# Signal_Conditioner.net
KiCad netlist of a schematic drawn in Altium Designer
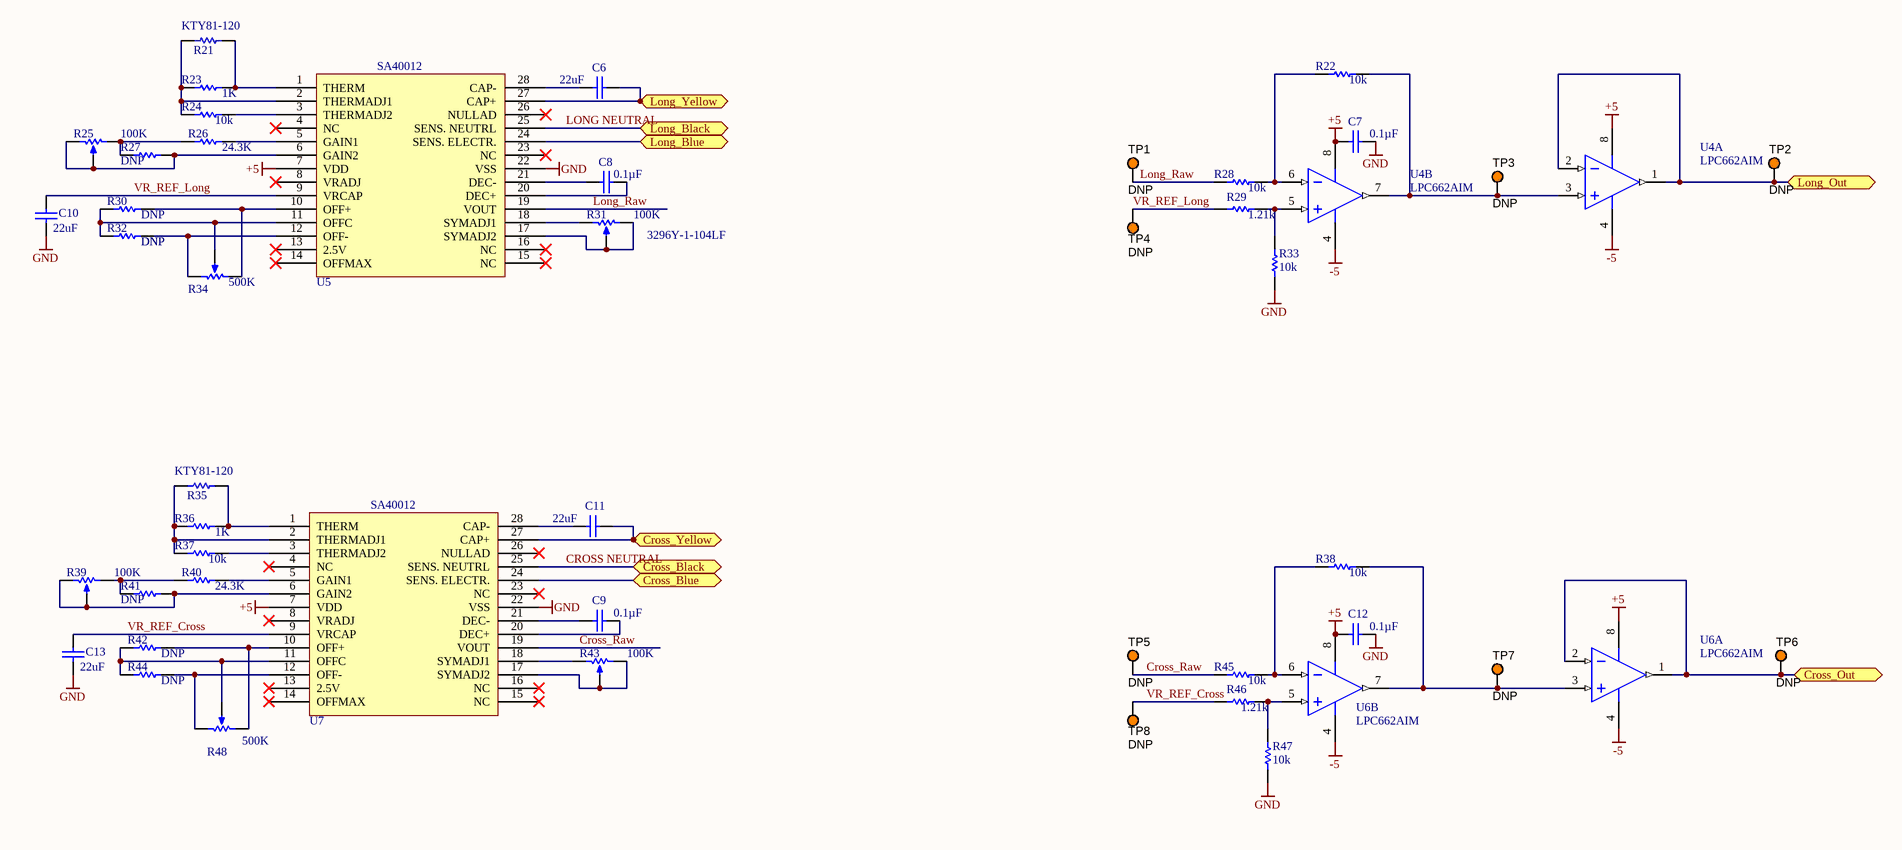
[diagram p0: Signal_Conditioner.SchDoc]

(export (version "E")
  (design (tool "Eeschema 10.0.6"))
  (components
    (comp (ref "C6")
      (value "22uF")
      (footprint "CAPC0805(2012)145_N")
      (description "CAP CER 22UF 16V X5R 0805")
      (fields
        (field (name "MANUFACTURER") "Murata Electronics North America")
        (field (name "MANUFACTURER PART NUMBER") "GRM219R61C226ME15L")
      )
      (libsource (lib "Altium Content Vault") (part "CMP-1036-04795-1"))
    )
    (comp (ref "C7")
      (value "CAP CER 0.1UF 25V X7R 0805")
      (footprint "CAPC0805(2012)145_N")
      (fields
        (field (name "MANUFACTURER") "Murata Electronics North America")
        (field (name "MANUFACTURER PART NUMBER") "GRM21BR71E104KA01L")
        (field (name "CAPACITANCE") "0.1µF")
        (field (name "TOLERANCE") "±10%")
      )
      (libsource (lib "Altium Content Vault") (part "CMP-1036-04795-1"))
    )
    (comp (ref "C8")
      (value "CAP CER 0.1UF 25V X7R 0805")
      (footprint "CAPC0805(2012)145_N")
      (fields
        (field (name "MANUFACTURER") "Murata Electronics North America")
        (field (name "MANUFACTURER PART NUMBER") "GRM21BR71E104KA01L")
        (field (name "CAPACITANCE") "0.1µF")
        (field (name "TOLERANCE") "±10%")
      )
      (libsource (lib "Altium Content Vault") (part "CMP-1036-04795-1"))
    )
    (comp (ref "C9")
      (value "CAP CER 0.1UF 25V X7R 0805")
      (footprint "CAPC0805(2012)145_N")
      (fields
        (field (name "MANUFACTURER") "Murata Electronics North America")
        (field (name "MANUFACTURER PART NUMBER") "GRM21BR71E104KA01L")
        (field (name "CAPACITANCE") "0.1µF")
        (field (name "TOLERANCE") "±10%")
      )
      (libsource (lib "Altium Content Vault") (part "CMP-1036-04795-1"))
    )
    (comp (ref "C10")
      (value "22uF")
      (footprint "CAPC0805(2012)145_N")
      (description "CAP CER 22UF 16V X5R 0805")
      (fields
        (field (name "MANUFACTURER") "Murata Electronics North America")
        (field (name "MANUFACTURER PART NUMBER") "GRM219R61C226ME15L")
      )
      (libsource (lib "Altium Content Vault") (part "CMP-1036-04795-1"))
    )
    (comp (ref "C11")
      (value "22uF")
      (footprint "CAPC0805(2012)145_N")
      (description "CAP CER 22UF 16V X5R 0805")
      (fields
        (field (name "MANUFACTURER") "Murata Electronics North America")
        (field (name "MANUFACTURER PART NUMBER") "GRM219R61C226ME15L")
      )
      (libsource (lib "Altium Content Vault") (part "CMP-1036-04795-1"))
    )
    (comp (ref "C12")
      (value "CAP CER 0.1UF 25V X7R 0805")
      (footprint "CAPC0805(2012)145_N")
      (fields
        (field (name "MANUFACTURER") "Murata Electronics North America")
        (field (name "MANUFACTURER PART NUMBER") "GRM21BR71E104KA01L")
        (field (name "CAPACITANCE") "0.1µF")
        (field (name "TOLERANCE") "±10%")
      )
      (libsource (lib "Altium Content Vault") (part "CMP-1036-04795-1"))
    )
    (comp (ref "C13")
      (value "22uF")
      (footprint "CAPC0805(2012)145_N")
      (description "CAP CER 22UF 16V X5R 0805")
      (fields
        (field (name "MANUFACTURER") "Murata Electronics North America")
        (field (name "MANUFACTURER PART NUMBER") "GRM219R61C226ME15L")
      )
      (libsource (lib "Altium Content Vault") (part "CMP-1036-04795-1"))
    )
    (comp (ref "R21")
      (value "KTY81-120")
      (footprint "KTY81-120")
      (description "THERMISTOR PTC 1K OHM PBCYT2")
      (fields
        (field (name "MANUFACTURER") "NXP USA Inc.")
        (field (name "MANUFACTURER PART NUMBER") "KTY81/120,112")
      )
      (libsource (lib "ZLS_Schematic_lib") (part "KTY81-120"))
    )
    (comp (ref "R22")
      (value "10k")
      (footprint "RESC0805(2012)_L")
      (description "RES SMD 10K OHM 1% 1/8W 0805")
      (fields
        (field (name "MANUFACTURER") "Vishay Dale")
        (field (name "MANUFACTURER PART NUMBER") "CRCW080510K0FKEA")
      )
      (libsource (lib "Altium Content Vault") (part "CMP-1013-00393-1"))
    )
    (comp (ref "R23")
      (value "1K")
      (footprint "RESC0805(2012)_L")
      (description "RES SMD 1K OHM 1% 1/8W 0805")
      (fields
        (field (name "MANUFACTURER") "Vishay Dale")
        (field (name "MANUFACTURER PART NUMBER") "CRCW08051K00FKEA")
      )
      (libsource (lib "Altium Content Vault") (part "CMP-1013-00393-1"))
    )
    (comp (ref "R24")
      (value "10k")
      (footprint "RESC0805(2012)_L")
      (description "RES SMD 10K OHM 1% 1/8W 0805")
      (fields
        (field (name "MANUFACTURER") "Vishay Dale")
        (field (name "MANUFACTURER PART NUMBER") "CRCW080510K0FKEA")
      )
      (libsource (lib "Altium Content Vault") (part "CMP-1013-00393-1"))
    )
    (comp (ref "R25")
      (value "100K")
      (footprint "Trimmer 2.54")
      (description "TRIMMER 5K OHM 0.25W PC PIN")
      (fields
        (field (name "MANUFACTURER") "Bourns Inc.")
        (field (name "MANUFACTURER PART NUMBER") "3296Y-1-104LF")
      )
      (libsource (lib "ZLS_Schematic_lib") (part "Trimmer"))
    )
    (comp (ref "R26")
      (value "24.3K")
      (footprint "RESC0805(2012)_L")
      (description "RES SMD 24.3K OHM 1% 1/8W 0805")
      (fields
        (field (name "MANUFACTURER") "Vishay Dale")
        (field (name "MANUFACTURER PART NUMBER") "CRCW080524K3FKEA")
      )
      (libsource (lib "Altium Content Vault") (part "CMP-1013-00393-1"))
    )
    (comp (ref "R27")
      (value "DNP")
      (footprint "RESC0805(2012)_L")
      (description "RES SMD 10K OHM 1% 1/8W 0805")
      (fields
        (field (name "MANUFACTURER") "Vishay Dale")
        (field (name "MANUFACTURER PART NUMBER") "CRCW080510K0FKEA")
      )
      (libsource (lib "Altium Content Vault") (part "CMP-1013-00393-1"))
    )
    (comp (ref "R28")
      (value "10k")
      (footprint "RESC0805(2012)_L")
      (description "RES SMD 10K OHM 1% 1/8W 0805")
      (fields
        (field (name "MANUFACTURER") "Vishay Dale")
        (field (name "MANUFACTURER PART NUMBER") "CRCW080510K0FKEA")
      )
      (libsource (lib "Altium Content Vault") (part "CMP-1013-00393-1"))
    )
    (comp (ref "R29")
      (value "1.21k")
      (footprint "RESC0805(2012)_L")
      (description "RES SMD 1.21K OHM 1% 1/8W 0805")
      (fields
        (field (name "MANUFACTURER") "Vishay Dale")
        (field (name "MANUFACTURER PART NUMBER") "CRCW08051K21FKEA")
      )
      (libsource (lib "Altium Content Vault") (part "CMP-1013-00393-1"))
    )
    (comp (ref "R30")
      (value "DNP")
      (footprint "RESC0805(2012)_L")
      (description "RES SMD 249K OHM 1% 1/8W 0805")
      (fields
        (field (name "MANUFACTURER") "Vishay Dale")
        (field (name "MANUFACTURER PART NUMBER") "CRCW0805249KFKECC")
      )
      (libsource (lib "Altium Content Vault") (part "CMP-1013-00393-1"))
    )
    (comp (ref "R31")
      (value "100K")
      (footprint "Trimmer 2.54")
      (description "TRIMMER 5K OHM 0.25W PC PIN")
      (fields
        (field (name "MANUFACTURER") "Bourns Inc.")
        (field (name "MANUFACTURER PART NUMBER") "3296Y-1-104LF")
      )
      (libsource (lib "ZLS_Schematic_lib") (part "Trimmer"))
    )
    (comp (ref "R32")
      (value "DNP")
      (footprint "RESC0805(2012)_L")
      (description "RES SMD 249K OHM 1% 1/8W 0805")
      (fields
        (field (name "MANUFACTURER") "Vishay Dale")
        (field (name "MANUFACTURER PART NUMBER") "CRCW0805249KFKECC")
      )
      (libsource (lib "Altium Content Vault") (part "CMP-1013-00393-1"))
    )
    (comp (ref "R33")
      (value "10k")
      (footprint "RESC0805(2012)_L")
      (description "RES SMD 10K OHM 1% 1/8W 0805")
      (fields
        (field (name "MANUFACTURER") "Vishay Dale")
        (field (name "MANUFACTURER PART NUMBER") "CRCW080510K0FKEA")
      )
      (libsource (lib "Altium Content Vault") (part "CMP-1013-00393-1"))
    )
    (comp (ref "R34")
      (value "500K")
      (footprint "Trimmer 2.54")
      (description "TRIMMER 500K OHM 0.5W PC PIN TOP")
      (fields
        (field (name "MANUFACTURER") "Bourns Inc.")
        (field (name "MANUFACTURER PART NUMBER") "3296Y-1-504LF")
      )
      (libsource (lib "ZLS_Schematic_lib") (part "Trimmer"))
    )
    (comp (ref "R35")
      (value "KTY81-120")
      (footprint "KTY81-120")
      (description "THERMISTOR PTC 1K OHM PBCYT2")
      (fields
        (field (name "MANUFACTURER") "NXP USA Inc.")
        (field (name "MANUFACTURER PART NUMBER") "KTY81/120,112")
      )
      (libsource (lib "ZLS_Schematic_lib") (part "KTY81-120"))
    )
    (comp (ref "R36")
      (value "1K")
      (footprint "RESC0805(2012)_L")
      (description "RES SMD 1K OHM 1% 1/8W 0805")
      (fields
        (field (name "MANUFACTURER") "Vishay Dale")
        (field (name "MANUFACTURER PART NUMBER") "CRCW08051K00FKEA")
      )
      (libsource (lib "Altium Content Vault") (part "CMP-1013-00393-1"))
    )
    (comp (ref "R37")
      (value "10k")
      (footprint "RESC0805(2012)_L")
      (description "RES SMD 10K OHM 1% 1/8W 0805")
      (fields
        (field (name "MANUFACTURER") "Vishay Dale")
        (field (name "MANUFACTURER PART NUMBER") "CRCW080510K0FKEA")
      )
      (libsource (lib "Altium Content Vault") (part "CMP-1013-00393-1"))
    )
    (comp (ref "R38")
      (value "10k")
      (footprint "RESC0805(2012)_L")
      (description "RES SMD 10K OHM 1% 1/8W 0805")
      (fields
        (field (name "MANUFACTURER") "Vishay Dale")
        (field (name "MANUFACTURER PART NUMBER") "CRCW080510K0FKEA")
      )
      (libsource (lib "Altium Content Vault") (part "CMP-1013-00393-1"))
    )
    (comp (ref "R39")
      (value "100K")
      (footprint "Trimmer 2.54")
      (description "TRIMMER 5K OHM 0.25W PC PIN")
      (fields
        (field (name "MANUFACTURER") "Bourns Inc.")
        (field (name "MANUFACTURER PART NUMBER") "3296Y-1-104LF")
      )
      (libsource (lib "ZLS_Schematic_lib") (part "Trimmer"))
    )
    (comp (ref "R40")
      (value "24.3K")
      (footprint "RESC0805(2012)_L")
      (description "RES SMD 24.3K OHM 1% 1/8W 0805")
      (fields
        (field (name "MANUFACTURER") "Vishay Dale")
        (field (name "MANUFACTURER PART NUMBER") "CRCW080524K3FKEA")
      )
      (libsource (lib "Altium Content Vault") (part "CMP-1013-00393-1"))
    )
    (comp (ref "R41")
      (value "DNP")
      (footprint "RESC0805(2012)_L")
      (description "RES SMD 10K OHM 1% 1/8W 0805")
      (fields
        (field (name "MANUFACTURER") "Vishay Dale")
        (field (name "MANUFACTURER PART NUMBER") "CRCW080510K0FKEA")
      )
      (libsource (lib "Altium Content Vault") (part "CMP-1013-00393-1"))
    )
    (comp (ref "R42")
      (value "DNP")
      (footprint "RESC0805(2012)_L")
      (description "RES SMD 249K OHM 1% 1/8W 0805")
      (fields
        (field (name "MANUFACTURER") "Vishay Dale")
        (field (name "MANUFACTURER PART NUMBER") "CRCW0805249KFKECC")
      )
      (libsource (lib "Altium Content Vault") (part "CMP-1013-00393-1"))
    )
    (comp (ref "R43")
      (value "100K")
      (footprint "Trimmer 2.54")
      (description "TRIMMER 5K OHM 0.25W PC PIN")
      (fields
        (field (name "MANUFACTURER") "Bourns Inc.")
        (field (name "MANUFACTURER PART NUMBER") "3296Y-1-104LF")
      )
      (libsource (lib "ZLS_Schematic_lib") (part "Trimmer"))
    )
    (comp (ref "R44")
      (value "DNP")
      (footprint "RESC0805(2012)_L")
      (description "RES SMD 249K OHM 1% 1/8W 0805")
      (fields
        (field (name "MANUFACTURER") "Vishay Dale")
        (field (name "MANUFACTURER PART NUMBER") "CRCW0805249KFKECC")
      )
      (libsource (lib "Altium Content Vault") (part "CMP-1013-00393-1"))
    )
    (comp (ref "R45")
      (value "10k")
      (footprint "RESC0805(2012)_L")
      (description "RES SMD 10K OHM 1% 1/8W 0805")
      (fields
        (field (name "MANUFACTURER") "Vishay Dale")
        (field (name "MANUFACTURER PART NUMBER") "CRCW080510K0FKEA")
      )
      (libsource (lib "Altium Content Vault") (part "CMP-1013-00393-1"))
    )
    (comp (ref "R46")
      (value "1.21k")
      (footprint "RESC0805(2012)_L")
      (description "RES SMD 1.21K OHM 1% 1/8W 0805")
      (fields
        (field (name "MANUFACTURER") "Vishay Dale")
        (field (name "MANUFACTURER PART NUMBER") "CRCW08051K21FKEA")
      )
      (libsource (lib "Altium Content Vault") (part "CMP-1013-00393-1"))
    )
    (comp (ref "R47")
      (value "10k")
      (footprint "RESC0805(2012)_L")
      (description "RES SMD 10K OHM 1% 1/8W 0805")
      (fields
        (field (name "MANUFACTURER") "Vishay Dale")
        (field (name "MANUFACTURER PART NUMBER") "CRCW080510K0FKEA")
      )
      (libsource (lib "Altium Content Vault") (part "CMP-1013-00393-1"))
    )
    (comp (ref "R48")
      (value "500K")
      (footprint "Trimmer 2.54")
      (description "TRIMMER 500K OHM 0.5W PC PIN TOP")
      (fields
        (field (name "MANUFACTURER") "Bourns Inc.")
        (field (name "MANUFACTURER PART NUMBER") "3296Y-1-504LF")
      )
      (libsource (lib "ZLS_Schematic_lib") (part "Trimmer"))
    )
    (comp (ref "TP1")
      (value "DNP")
      (footprint "KSTN-5003")
      (description "Test Point, Orange, 1-Pin THD, RoHS")
      (fields
        (field (name "MANUFACTURER") "Keystone Electronics")
        (field (name "MANUFACTURER PART NUMBER") "5003")
      )
      (libsource (lib "Altium Content Vault") (part "CMP-1672-00009-1"))
    )
    (comp (ref "TP2")
      (value "DNP")
      (footprint "KSTN-5003")
      (description "Test Point, Orange, 1-Pin THD, RoHS")
      (fields
        (field (name "MANUFACTURER") "Keystone Electronics")
        (field (name "MANUFACTURER PART NUMBER") "5003")
      )
      (libsource (lib "Altium Content Vault") (part "CMP-1672-00009-1"))
    )
    (comp (ref "TP3")
      (value "DNP")
      (footprint "KSTN-5003")
      (description "Test Point, Orange, 1-Pin THD, RoHS")
      (fields
        (field (name "MANUFACTURER") "Keystone Electronics")
        (field (name "MANUFACTURER PART NUMBER") "5003")
      )
      (libsource (lib "Altium Content Vault") (part "CMP-1672-00009-1"))
    )
    (comp (ref "TP4")
      (value "DNP")
      (footprint "KSTN-5003")
      (description "Test Point, Orange, 1-Pin THD, RoHS")
      (fields
        (field (name "MANUFACTURER") "Keystone Electronics")
        (field (name "MANUFACTURER PART NUMBER") "5003")
      )
      (libsource (lib "Altium Content Vault") (part "CMP-1672-00009-1"))
    )
    (comp (ref "TP5")
      (value "DNP")
      (footprint "KSTN-5003")
      (description "Test Point, Orange, 1-Pin THD, RoHS")
      (fields
        (field (name "MANUFACTURER") "Keystone Electronics")
        (field (name "MANUFACTURER PART NUMBER") "5003")
      )
      (libsource (lib "Altium Content Vault") (part "CMP-1672-00009-1"))
    )
    (comp (ref "TP6")
      (value "DNP")
      (footprint "KSTN-5003")
      (description "Test Point, Orange, 1-Pin THD, RoHS")
      (fields
        (field (name "MANUFACTURER") "Keystone Electronics")
        (field (name "MANUFACTURER PART NUMBER") "5003")
      )
      (libsource (lib "Altium Content Vault") (part "CMP-1672-00009-1"))
    )
    (comp (ref "TP7")
      (value "DNP")
      (footprint "KSTN-5003")
      (description "Test Point, Orange, 1-Pin THD, RoHS")
      (fields
        (field (name "MANUFACTURER") "Keystone Electronics")
        (field (name "MANUFACTURER PART NUMBER") "5003")
      )
      (libsource (lib "Altium Content Vault") (part "CMP-1672-00009-1"))
    )
    (comp (ref "TP8")
      (value "DNP")
      (footprint "KSTN-5003")
      (description "Test Point, Orange, 1-Pin THD, RoHS")
      (fields
        (field (name "MANUFACTURER") "Keystone Electronics")
        (field (name "MANUFACTURER PART NUMBER") "5003")
      )
      (libsource (lib "Altium Content Vault") (part "CMP-1672-00009-1"))
    )
    (comp (ref "U4")
      (value "LPC662AIM")
      (footprint "D0008A_M")
      (description "Low Power CMOS Dual Operational Amplifier, 8-pin Narrow SOIC")
      (fields (field (name "MANUFACTURER") "Texas Instruments"))
      (libsource (lib "Altium Content Vault") (part "AMP-OPA-LM6132-8"))
    )
    (comp (ref "U5")
      (value "SA40012")
      (footprint "SA40012")
      (description "Single Axix CMOS Signal Conditioning Module")
      (fields (field (name "MANUFACTURER") "Spectron") (field (name "MANUFACTURER PART NUMBER") "A40012"))
      (libsource (lib "ZLS_Schematic_lib") (part "SA40012"))
    )
    (comp (ref "U6")
      (value "LPC662AIM")
      (footprint "D0008A_M")
      (description "Low Power CMOS Dual Operational Amplifier, 8-pin Narrow SOIC")
      (fields
        (field (name "MANUFACTURER") "Texas Instruments")
        (field (name "MANUFACTURER PART NUMBER") "LPC662AIMX/NOPB")
      )
      (libsource (lib "Altium Content Vault") (part "CMP-0055-00867-3"))
    )
    (comp (ref "U7")
      (value "SA40012")
      (footprint "SA40012")
      (description "Single Axix CMOS Signal Conditioning Module")
      (fields (field (name "MANUFACTURER") "Spectron") (field (name "MANUFACTURER PART NUMBER") "A40012"))
      (libsource (lib "ZLS_Schematic_lib") (part "SA40012"))
    )
  )
  (nets
    (net (code "1") (name "+5") (class "Default")
      (node (ref "C12") (pin "1") (pinfunction "1_1") (pintype "passive"))
      (node (ref "C7") (pin "1") (pinfunction "1_1") (pintype "passive"))
      (node (ref "U4") (pin "8") (pinfunction "V+_8") (pintype "power_in"))
      (node (ref "U5") (pin "7") (pinfunction "VDD_7") (pintype "passive"))
      (node (ref "U6") (pin "8") (pinfunction "V+_8") (pintype "power_in"))
      (node (ref "U7") (pin "7") (pinfunction "VDD_7") (pintype "passive"))
    )
    (net (code "2") (name "-5") (class "Default")
      (node (ref "U4") (pin "4") (pinfunction "V-_4") (pintype "power_in"))
      (node (ref "U6") (pin "4") (pinfunction "V-_4") (pintype "power_in"))
    )
    (net (code "3") (name "/CROSS NEUTRAL") (class "Default")
      (node (ref "U7") (pin "25") (pinfunction "SENS._NEUTRL_25") (pintype "passive"))
    )
    (net (code "4") (name "/Cross_Blue") (class "Default")
      (node (ref "U7") (pin "24") (pinfunction "SENS._ELECTR._24") (pintype "passive"))
    )
    (net (code "5") (name "/Cross_Out") (class "Default")
      (node (ref "TP6") (pin "1") (pinfunction "1_1") (pintype "passive"))
      (node (ref "U6") (pin "1") (pinfunction "OUTA_1") (pintype "output"))
      (node (ref "U6") (pin "2") (pinfunction "INA-_2") (pintype "input"))
    )
    (net (code "6") (name "/Cross_Raw") (class "Default")
      (node (ref "R45") (pin "1") (pinfunction "1_1") (pintype "passive"))
      (node (ref "TP5") (pin "1") (pinfunction "1_1") (pintype "passive"))
      (node (ref "U7") (pin "19") (pinfunction "VOUT_19") (pintype "passive"))
    )
    (net (code "7") (name "/Cross_Yellow") (class "Default")
      (node (ref "C11") (pin "2") (pinfunction "2_2") (pintype "passive"))
      (node (ref "U7") (pin "27") (pinfunction "CAP+_27") (pintype "passive"))
    )
    (net (code "8") (name "/LONG NEUTRAL") (class "Default")
      (node (ref "U5") (pin "25") (pinfunction "SENS._NEUTRL_25") (pintype "passive"))
    )
    (net (code "9") (name "/Long_Blue") (class "Default")
      (node (ref "U5") (pin "24") (pinfunction "SENS._ELECTR._24") (pintype "passive"))
    )
    (net (code "10") (name "/Long_Out") (class "Default")
      (node (ref "TP2") (pin "1") (pinfunction "1_1") (pintype "passive"))
      (node (ref "U4") (pin "1") (pinfunction "OUTA_1") (pintype "output"))
      (node (ref "U4") (pin "2") (pinfunction "INA-_2") (pintype "input"))
    )
    (net (code "11") (name "/Long_Raw") (class "Default")
      (node (ref "R28") (pin "1") (pinfunction "1_1") (pintype "passive"))
      (node (ref "TP1") (pin "1") (pinfunction "1_1") (pintype "passive"))
      (node (ref "U5") (pin "19") (pinfunction "VOUT_19") (pintype "passive"))
    )
    (net (code "12") (name "/Long_Yellow") (class "Default")
      (node (ref "C6") (pin "2") (pinfunction "2_2") (pintype "passive"))
      (node (ref "U5") (pin "27") (pinfunction "CAP+_27") (pintype "passive"))
    )
    (net (code "13") (name "/VR_REF_Cross") (class "Default")
      (node (ref "C13") (pin "1") (pinfunction "1_1") (pintype "passive"))
      (node (ref "R46") (pin "2") (pinfunction "2_2") (pintype "passive"))
      (node (ref "TP8") (pin "1") (pinfunction "1_1") (pintype "passive"))
      (node (ref "U7") (pin "9") (pinfunction "VRCAP_9") (pintype "passive"))
    )
    (net (code "14") (name "/VR_REF_Long") (class "Default")
      (node (ref "C10") (pin "1") (pinfunction "1_1") (pintype "passive"))
      (node (ref "R29") (pin "2") (pinfunction "2_2") (pintype "passive"))
      (node (ref "TP4") (pin "1") (pinfunction "1_1") (pintype "passive"))
      (node (ref "U5") (pin "9") (pinfunction "VRCAP_9") (pintype "passive"))
    )
    (net (code "15") (name "GND") (class "Default")
      (node (ref "C10") (pin "2") (pinfunction "2_2") (pintype "passive"))
      (node (ref "C12") (pin "2") (pinfunction "2_2") (pintype "passive"))
      (node (ref "C13") (pin "2") (pinfunction "2_2") (pintype "passive"))
      (node (ref "C7") (pin "2") (pinfunction "2_2") (pintype "passive"))
      (node (ref "R33") (pin "1") (pinfunction "1_1") (pintype "passive"))
      (node (ref "R47") (pin "1") (pinfunction "1_1") (pintype "passive"))
      (node (ref "U5") (pin "22") (pinfunction "VSS_22") (pintype "passive"))
      (node (ref "U7") (pin "22") (pinfunction "VSS_22") (pintype "passive"))
    )
    (net (code "16") (name "Net-(R25-a)") (class "Default")
      (node (ref "R25") (pin "1") (pinfunction "a_1") (pintype "passive"))
      (node (ref "R25") (pin "2") (pinfunction "b_2") (pintype "passive"))
      (node (ref "R27") (pin "2") (pinfunction "2_2") (pintype "passive"))
      (node (ref "U5") (pin "6") (pinfunction "GAIN2_6") (pintype "passive"))
    )
    (net (code "17") (name "Net-(R25-c)") (class "Default")
      (node (ref "R25") (pin "3") (pinfunction "c_3") (pintype "passive"))
      (node (ref "R26") (pin "1") (pinfunction "1_1") (pintype "passive"))
      (node (ref "R27") (pin "1") (pinfunction "1_1") (pintype "passive"))
    )
    (net (code "18") (name "Net-(R31-a)") (class "Default")
      (node (ref "R31") (pin "1") (pinfunction "a_1") (pintype "passive"))
      (node (ref "U5") (pin "18") (pinfunction "SYMADJ1_18") (pintype "passive"))
    )
    (net (code "19") (name "Net-(R31-b)") (class "Default")
      (node (ref "R31") (pin "2") (pinfunction "b_2") (pintype "passive"))
      (node (ref "R31") (pin "3") (pinfunction "c_3") (pintype "passive"))
      (node (ref "U5") (pin "17") (pinfunction "SYMADJ2_17") (pintype "passive"))
    )
    (net (code "20") (name "Net-(R34-a)") (class "Default")
      (node (ref "R30") (pin "2") (pinfunction "2_2") (pintype "passive"))
      (node (ref "R34") (pin "1") (pinfunction "a_1") (pintype "passive"))
      (node (ref "U5") (pin "10") (pinfunction "OFF+_10") (pintype "passive"))
    )
    (net (code "21") (name "Net-(R34-b)") (class "Default")
      (node (ref "R30") (pin "1") (pinfunction "1_1") (pintype "passive"))
      (node (ref "R32") (pin "1") (pinfunction "1_1") (pintype "passive"))
      (node (ref "R34") (pin "2") (pinfunction "b_2") (pintype "passive"))
      (node (ref "U5") (pin "11") (pinfunction "OFFC_11") (pintype "passive"))
    )
    (net (code "22") (name "Net-(R34-c)") (class "Default")
      (node (ref "R32") (pin "2") (pinfunction "2_2") (pintype "passive"))
      (node (ref "R34") (pin "3") (pinfunction "c_3") (pintype "passive"))
      (node (ref "U5") (pin "12") (pinfunction "OFF-_12") (pintype "passive"))
    )
    (net (code "23") (name "Net-(R39-a)") (class "Default")
      (node (ref "R39") (pin "1") (pinfunction "a_1") (pintype "passive"))
      (node (ref "R39") (pin "2") (pinfunction "b_2") (pintype "passive"))
      (node (ref "R41") (pin "2") (pinfunction "2_2") (pintype "passive"))
      (node (ref "U7") (pin "6") (pinfunction "GAIN2_6") (pintype "passive"))
    )
    (net (code "24") (name "Net-(R39-c)") (class "Default")
      (node (ref "R39") (pin "3") (pinfunction "c_3") (pintype "passive"))
      (node (ref "R40") (pin "1") (pinfunction "1_1") (pintype "passive"))
      (node (ref "R41") (pin "1") (pinfunction "1_1") (pintype "passive"))
    )
    (net (code "25") (name "Net-(R43-a)") (class "Default")
      (node (ref "R43") (pin "1") (pinfunction "a_1") (pintype "passive"))
      (node (ref "U7") (pin "18") (pinfunction "SYMADJ1_18") (pintype "passive"))
    )
    (net (code "26") (name "Net-(R43-b)") (class "Default")
      (node (ref "R43") (pin "2") (pinfunction "b_2") (pintype "passive"))
      (node (ref "R43") (pin "3") (pinfunction "c_3") (pintype "passive"))
      (node (ref "U7") (pin "17") (pinfunction "SYMADJ2_17") (pintype "passive"))
    )
    (net (code "27") (name "Net-(R48-a)") (class "Default")
      (node (ref "R42") (pin "2") (pinfunction "2_2") (pintype "passive"))
      (node (ref "R48") (pin "1") (pinfunction "a_1") (pintype "passive"))
      (node (ref "U7") (pin "10") (pinfunction "OFF+_10") (pintype "passive"))
    )
    (net (code "28") (name "Net-(R48-b)") (class "Default")
      (node (ref "R42") (pin "1") (pinfunction "1_1") (pintype "passive"))
      (node (ref "R44") (pin "1") (pinfunction "1_1") (pintype "passive"))
      (node (ref "R48") (pin "2") (pinfunction "b_2") (pintype "passive"))
      (node (ref "U7") (pin "11") (pinfunction "OFFC_11") (pintype "passive"))
    )
    (net (code "29") (name "Net-(R48-c)") (class "Default")
      (node (ref "R44") (pin "2") (pinfunction "2_2") (pintype "passive"))
      (node (ref "R48") (pin "3") (pinfunction "c_3") (pintype "passive"))
      (node (ref "U7") (pin "12") (pinfunction "OFF-_12") (pintype "passive"))
    )
    (net (code "30") (name "Net-(U4A-INA+)") (class "Default")
      (node (ref "R22") (pin "2") (pinfunction "2_2") (pintype "passive"))
      (node (ref "TP3") (pin "1") (pinfunction "1_1") (pintype "passive"))
      (node (ref "U4") (pin "3") (pinfunction "INA+_3") (pintype "input"))
      (node (ref "U4") (pin "7") (pinfunction "OUTB_7") (pintype "output"))
    )
    (net (code "31") (name "Net-(U4B-INB+)") (class "Default")
      (node (ref "R29") (pin "1") (pinfunction "1_1") (pintype "passive"))
      (node (ref "R33") (pin "2") (pinfunction "2_2") (pintype "passive"))
      (node (ref "U4") (pin "5") (pinfunction "INB+_5") (pintype "input"))
    )
    (net (code "32") (name "Net-(U4B-INB-)") (class "Default")
      (node (ref "R22") (pin "1") (pinfunction "1_1") (pintype "passive"))
      (node (ref "R28") (pin "2") (pinfunction "2_2") (pintype "passive"))
      (node (ref "U4") (pin "6") (pinfunction "INB-_6") (pintype "input"))
    )
    (net (code "33") (name "Net-(U5-CAP-)") (class "Default")
      (node (ref "C6") (pin "1") (pinfunction "1_1") (pintype "passive"))
      (node (ref "U5") (pin "28") (pinfunction "CAP-_28") (pintype "passive"))
    )
    (net (code "34") (name "Net-(U5-DEC+)") (class "Default")
      (node (ref "C8") (pin "2") (pinfunction "2_2") (pintype "passive"))
      (node (ref "U5") (pin "20") (pinfunction "DEC+_20") (pintype "passive"))
    )
    (net (code "35") (name "Net-(U5-DEC-)") (class "Default")
      (node (ref "C8") (pin "1") (pinfunction "1_1") (pintype "passive"))
      (node (ref "U5") (pin "21") (pinfunction "DEC-_21") (pintype "passive"))
    )
    (net (code "36") (name "Net-(U5-GAIN1)") (class "Default")
      (node (ref "R26") (pin "2") (pinfunction "2_2") (pintype "passive"))
      (node (ref "U5") (pin "5") (pinfunction "GAIN1_5") (pintype "passive"))
    )
    (net (code "37") (name "Net-(U5-THERM)") (class "Default")
      (node (ref "R21") (pin "2") (pinfunction "2_2") (pintype "passive"))
      (node (ref "R23") (pin "2") (pinfunction "2_2") (pintype "passive"))
      (node (ref "U5") (pin "1") (pinfunction "THERM_1") (pintype "passive"))
    )
    (net (code "38") (name "Net-(U5-THERMADJ1)") (class "Default")
      (node (ref "R21") (pin "1") (pinfunction "1_1") (pintype "passive"))
      (node (ref "R23") (pin "1") (pinfunction "1_1") (pintype "passive"))
      (node (ref "R24") (pin "1") (pinfunction "1_1") (pintype "passive"))
      (node (ref "U5") (pin "2") (pinfunction "THERMADJ1_2") (pintype "passive"))
    )
    (net (code "39") (name "Net-(U5-THERMADJ2)") (class "Default")
      (node (ref "R24") (pin "2") (pinfunction "2_2") (pintype "passive"))
      (node (ref "U5") (pin "3") (pinfunction "THERMADJ2_3") (pintype "passive"))
    )
    (net (code "40") (name "Net-(U6A-INA+)") (class "Default")
      (node (ref "R38") (pin "2") (pinfunction "2_2") (pintype "passive"))
      (node (ref "TP7") (pin "1") (pinfunction "1_1") (pintype "passive"))
      (node (ref "U6") (pin "3") (pinfunction "INA+_3") (pintype "input"))
      (node (ref "U6") (pin "7") (pinfunction "OUTB_7") (pintype "output"))
    )
    (net (code "41") (name "Net-(U6B-INB+)") (class "Default")
      (node (ref "R46") (pin "1") (pinfunction "1_1") (pintype "passive"))
      (node (ref "R47") (pin "2") (pinfunction "2_2") (pintype "passive"))
      (node (ref "U6") (pin "5") (pinfunction "INB+_5") (pintype "input"))
    )
    (net (code "42") (name "Net-(U6B-INB-)") (class "Default")
      (node (ref "R38") (pin "1") (pinfunction "1_1") (pintype "passive"))
      (node (ref "R45") (pin "2") (pinfunction "2_2") (pintype "passive"))
      (node (ref "U6") (pin "6") (pinfunction "INB-_6") (pintype "input"))
    )
    (net (code "43") (name "Net-(U7-CAP-)") (class "Default")
      (node (ref "C11") (pin "1") (pinfunction "1_1") (pintype "passive"))
      (node (ref "U7") (pin "28") (pinfunction "CAP-_28") (pintype "passive"))
    )
    (net (code "44") (name "Net-(U7-DEC+)") (class "Default")
      (node (ref "C9") (pin "2") (pinfunction "2_2") (pintype "passive"))
      (node (ref "U7") (pin "20") (pinfunction "DEC+_20") (pintype "passive"))
    )
    (net (code "45") (name "Net-(U7-DEC-)") (class "Default")
      (node (ref "C9") (pin "1") (pinfunction "1_1") (pintype "passive"))
      (node (ref "U7") (pin "21") (pinfunction "DEC-_21") (pintype "passive"))
    )
    (net (code "46") (name "Net-(U7-GAIN1)") (class "Default")
      (node (ref "R40") (pin "2") (pinfunction "2_2") (pintype "passive"))
      (node (ref "U7") (pin "5") (pinfunction "GAIN1_5") (pintype "passive"))
    )
    (net (code "47") (name "Net-(U7-THERM)") (class "Default")
      (node (ref "R35") (pin "2") (pinfunction "2_2") (pintype "passive"))
      (node (ref "R36") (pin "2") (pinfunction "2_2") (pintype "passive"))
      (node (ref "U7") (pin "1") (pinfunction "THERM_1") (pintype "passive"))
    )
    (net (code "48") (name "Net-(U7-THERMADJ1)") (class "Default")
      (node (ref "R35") (pin "1") (pinfunction "1_1") (pintype "passive"))
      (node (ref "R36") (pin "1") (pinfunction "1_1") (pintype "passive"))
      (node (ref "R37") (pin "1") (pinfunction "1_1") (pintype "passive"))
      (node (ref "U7") (pin "2") (pinfunction "THERMADJ1_2") (pintype "passive"))
    )
    (net (code "49") (name "Net-(U7-THERMADJ2)") (class "Default")
      (node (ref "R37") (pin "2") (pinfunction "2_2") (pintype "passive"))
      (node (ref "U7") (pin "3") (pinfunction "THERMADJ2_3") (pintype "passive"))
    )
    (net (code "50") (name "unconnected-(U5-2.5V-Pad13)") (class "Default")
      (node (ref "U5") (pin "13") (pinfunction "2.5V_13") (pintype "passive+no_connect"))
    )
    (net (code "51") (name "unconnected-(U5-NC-Pad4)") (class "Default")
      (node (ref "U5") (pin "4") (pinfunction "NC_4") (pintype "passive+no_connect"))
    )
    (net (code "52") (name "unconnected-(U5-NC-Pad15)") (class "Default")
      (node (ref "U5") (pin "15") (pinfunction "NC_15") (pintype "passive+no_connect"))
    )
    (net (code "53") (name "unconnected-(U5-NC-Pad16)") (class "Default")
      (node (ref "U5") (pin "16") (pinfunction "NC_16") (pintype "passive+no_connect"))
    )
    (net (code "54") (name "unconnected-(U5-NC-Pad23)") (class "Default")
      (node (ref "U5") (pin "23") (pinfunction "NC_23") (pintype "passive+no_connect"))
    )
    (net (code "55") (name "unconnected-(U5-NULLAD-Pad26)") (class "Default")
      (node (ref "U5") (pin "26") (pinfunction "NULLAD_26") (pintype "passive+no_connect"))
    )
    (net (code "56") (name "unconnected-(U5-OFFMAX-Pad14)") (class "Default")
      (node (ref "U5") (pin "14") (pinfunction "OFFMAX_14") (pintype "passive+no_connect"))
    )
    (net (code "57") (name "unconnected-(U5-VRADJ-Pad8)") (class "Default")
      (node (ref "U5") (pin "8") (pinfunction "VRADJ_8") (pintype "passive+no_connect"))
    )
    (net (code "58") (name "unconnected-(U7-2.5V-Pad13)") (class "Default")
      (node (ref "U7") (pin "13") (pinfunction "2.5V_13") (pintype "passive+no_connect"))
    )
    (net (code "59") (name "unconnected-(U7-NC-Pad4)") (class "Default")
      (node (ref "U7") (pin "4") (pinfunction "NC_4") (pintype "passive+no_connect"))
    )
    (net (code "60") (name "unconnected-(U7-NC-Pad15)") (class "Default")
      (node (ref "U7") (pin "15") (pinfunction "NC_15") (pintype "passive+no_connect"))
    )
    (net (code "61") (name "unconnected-(U7-NC-Pad16)") (class "Default")
      (node (ref "U7") (pin "16") (pinfunction "NC_16") (pintype "passive+no_connect"))
    )
    (net (code "62") (name "unconnected-(U7-NC-Pad23)") (class "Default")
      (node (ref "U7") (pin "23") (pinfunction "NC_23") (pintype "passive+no_connect"))
    )
    (net (code "63") (name "unconnected-(U7-NULLAD-Pad26)") (class "Default")
      (node (ref "U7") (pin "26") (pinfunction "NULLAD_26") (pintype "passive+no_connect"))
    )
    (net (code "64") (name "unconnected-(U7-OFFMAX-Pad14)") (class "Default")
      (node (ref "U7") (pin "14") (pinfunction "OFFMAX_14") (pintype "passive+no_connect"))
    )
    (net (code "65") (name "unconnected-(U7-VRADJ-Pad8)") (class "Default")
      (node (ref "U7") (pin "8") (pinfunction "VRADJ_8") (pintype "passive+no_connect"))
    )
  )
)
